# EIB_96Ch_YO.net
KiCad netlist of a schematic drawn in EAGLE
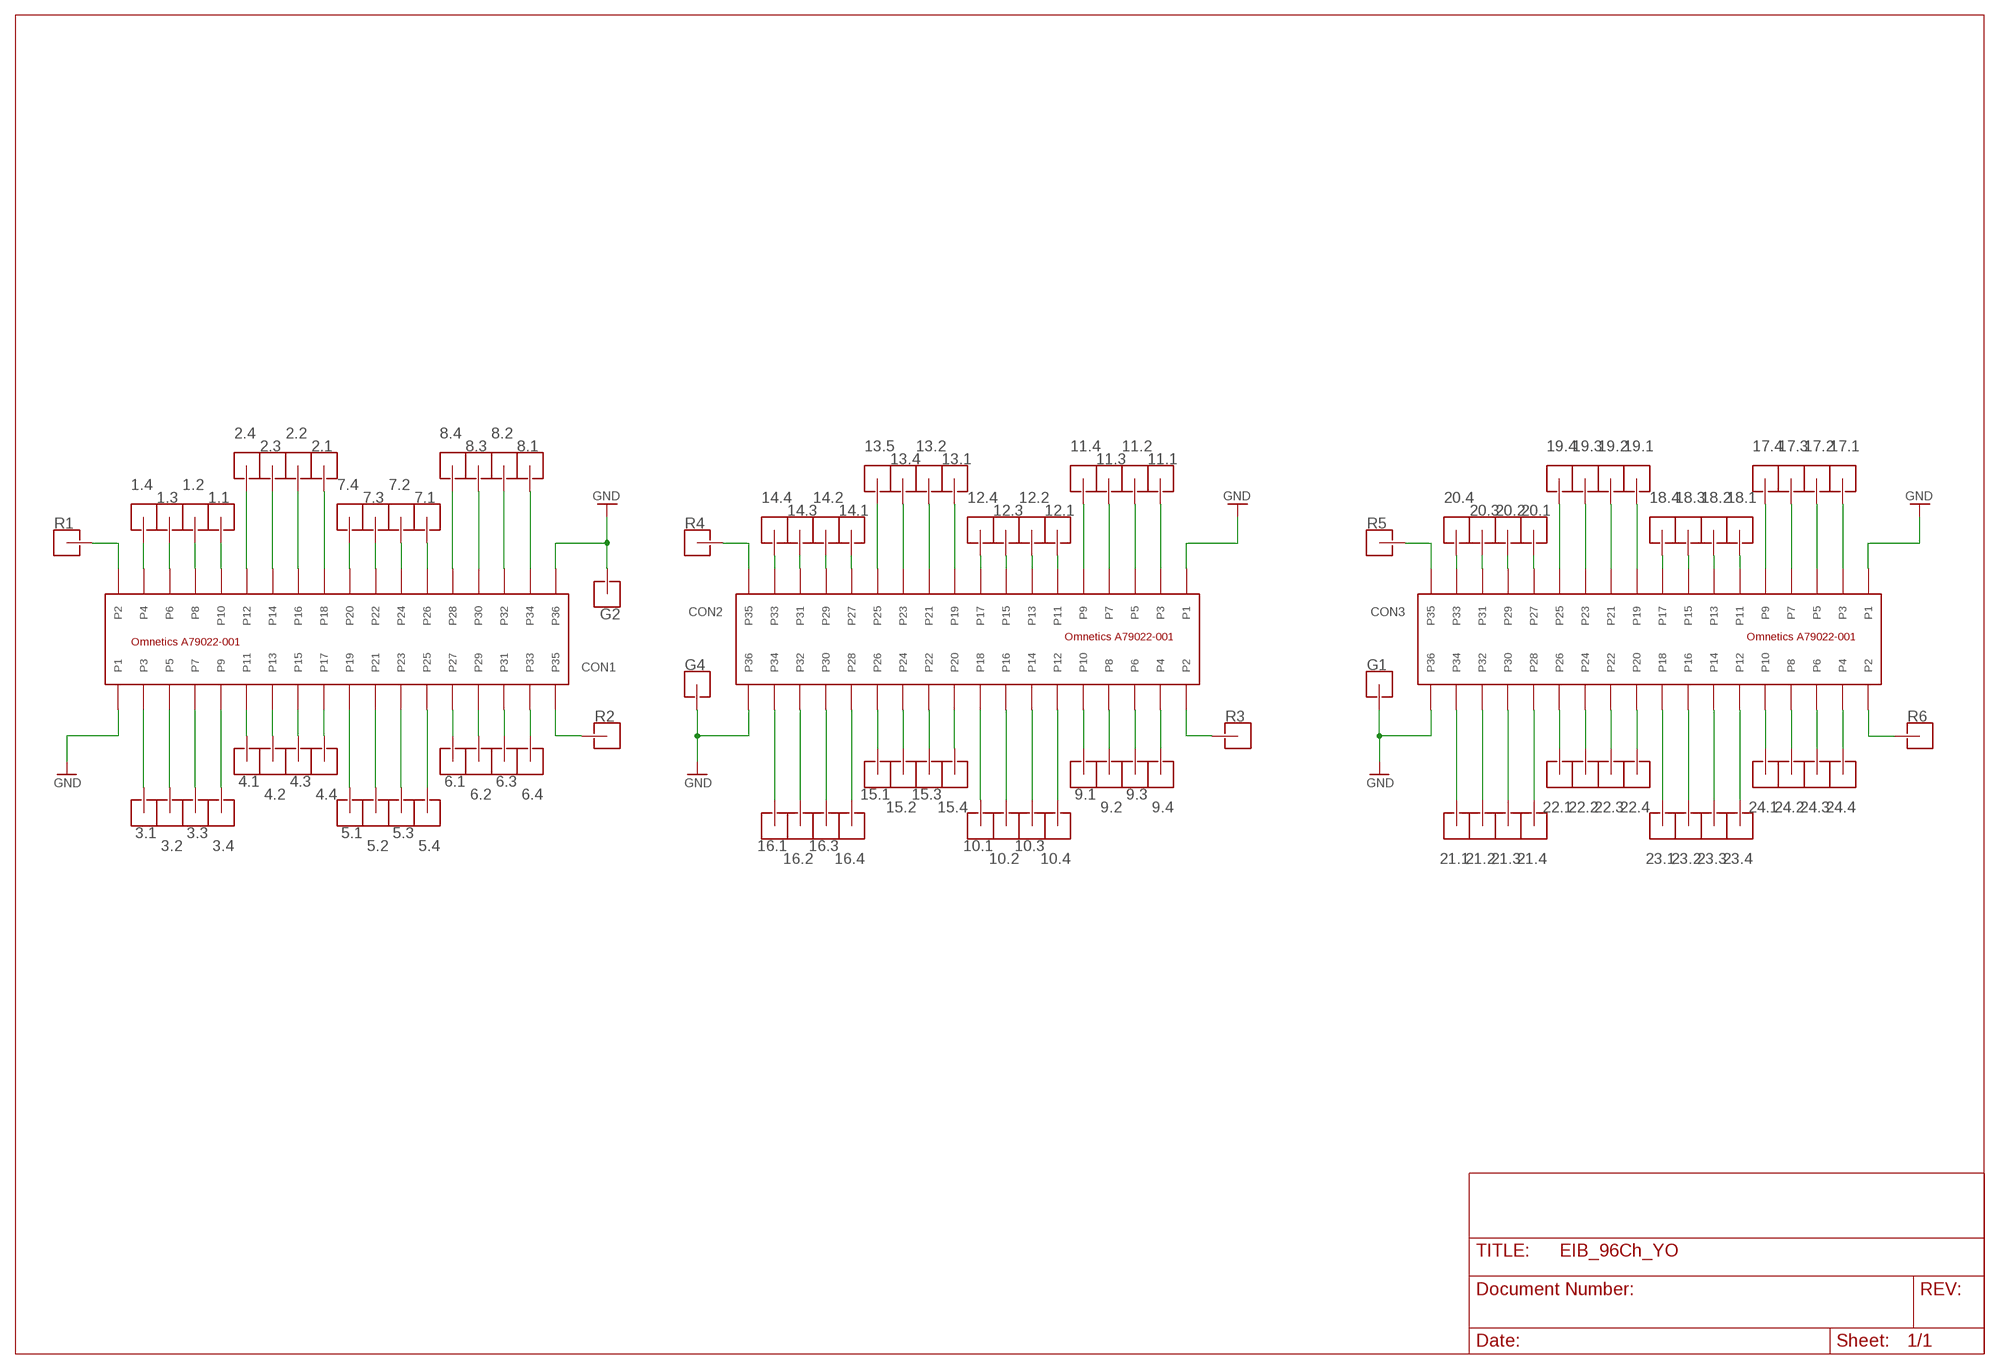
[diagram p0: schematic, sheet 1]

(export (version "E")
  (design (tool "Eeschema 10.0.6"))
  (components
    (comp (ref "1.1")
      (value "HOLE_L_G_PIN_V5")
      (footprint "eagle-import:LARGE_GOLD_PIN_V5")
      (libsource (lib "eagle-import") (part "HOLE_L_G_PIN_V5"))
    )
    (comp (ref "1.2")
      (value "HOLE_L_G_PIN_V5")
      (footprint "eagle-import:LARGE_GOLD_PIN_V5")
      (libsource (lib "eagle-import") (part "HOLE_L_G_PIN_V5"))
    )
    (comp (ref "1.3")
      (value "HOLE_L_G_PIN_V5")
      (footprint "eagle-import:LARGE_GOLD_PIN_V5")
      (libsource (lib "eagle-import") (part "HOLE_L_G_PIN_V5"))
    )
    (comp (ref "1.4")
      (value "HOLE_L_G_PIN_V5")
      (footprint "eagle-import:LARGE_GOLD_PIN_V5")
      (libsource (lib "eagle-import") (part "HOLE_L_G_PIN_V5"))
    )
    (comp (ref "2.1")
      (value "HOLE_L_G_PIN_V5")
      (footprint "eagle-import:LARGE_GOLD_PIN_V5")
      (libsource (lib "eagle-import") (part "HOLE_L_G_PIN_V5"))
    )
    (comp (ref "2.2")
      (value "HOLE_L_G_PIN_V5")
      (footprint "eagle-import:LARGE_GOLD_PIN_V5")
      (libsource (lib "eagle-import") (part "HOLE_L_G_PIN_V5"))
    )
    (comp (ref "2.3")
      (value "HOLE_L_G_PIN_V5")
      (footprint "eagle-import:LARGE_GOLD_PIN_V5")
      (libsource (lib "eagle-import") (part "HOLE_L_G_PIN_V5"))
    )
    (comp (ref "2.4")
      (value "HOLE_L_G_PIN_V5")
      (footprint "eagle-import:LARGE_GOLD_PIN_V5")
      (libsource (lib "eagle-import") (part "HOLE_L_G_PIN_V5"))
    )
    (comp (ref "3.1")
      (value "HOLE_L_G_PIN_V5")
      (footprint "eagle-import:LARGE_GOLD_PIN_V5")
      (libsource (lib "eagle-import") (part "HOLE_L_G_PIN_V5"))
    )
    (comp (ref "3.2")
      (value "HOLE_L_G_PIN_V5")
      (footprint "eagle-import:LARGE_GOLD_PIN_V5")
      (libsource (lib "eagle-import") (part "HOLE_L_G_PIN_V5"))
    )
    (comp (ref "3.3")
      (value "HOLE_L_G_PIN_V5")
      (footprint "eagle-import:LARGE_GOLD_PIN_V5")
      (libsource (lib "eagle-import") (part "HOLE_L_G_PIN_V5"))
    )
    (comp (ref "3.4")
      (value "HOLE_L_G_PIN_V5")
      (footprint "eagle-import:LARGE_GOLD_PIN_V5")
      (libsource (lib "eagle-import") (part "HOLE_L_G_PIN_V5"))
    )
    (comp (ref "4.1")
      (value "HOLE_L_G_PIN_V5")
      (footprint "eagle-import:LARGE_GOLD_PIN_V5")
      (libsource (lib "eagle-import") (part "HOLE_L_G_PIN_V5"))
    )
    (comp (ref "4.2")
      (value "HOLE_L_G_PIN_V5")
      (footprint "eagle-import:LARGE_GOLD_PIN_V5")
      (libsource (lib "eagle-import") (part "HOLE_L_G_PIN_V5"))
    )
    (comp (ref "4.3")
      (value "HOLE_L_G_PIN_V5")
      (footprint "eagle-import:LARGE_GOLD_PIN_V5")
      (libsource (lib "eagle-import") (part "HOLE_L_G_PIN_V5"))
    )
    (comp (ref "4.4")
      (value "HOLE_L_G_PIN_V5")
      (footprint "eagle-import:LARGE_GOLD_PIN_V5")
      (libsource (lib "eagle-import") (part "HOLE_L_G_PIN_V5"))
    )
    (comp (ref "5.1")
      (value "HOLE_L_G_PIN_V5")
      (footprint "eagle-import:LARGE_GOLD_PIN_V5")
      (libsource (lib "eagle-import") (part "HOLE_L_G_PIN_V5"))
    )
    (comp (ref "5.2")
      (value "HOLE_L_G_PIN_V5")
      (footprint "eagle-import:LARGE_GOLD_PIN_V5")
      (libsource (lib "eagle-import") (part "HOLE_L_G_PIN_V5"))
    )
    (comp (ref "5.3")
      (value "HOLE_L_G_PIN_V5")
      (footprint "eagle-import:LARGE_GOLD_PIN_V5")
      (libsource (lib "eagle-import") (part "HOLE_L_G_PIN_V5"))
    )
    (comp (ref "5.4")
      (value "HOLE_L_G_PIN_V5")
      (footprint "eagle-import:LARGE_GOLD_PIN_V5")
      (libsource (lib "eagle-import") (part "HOLE_L_G_PIN_V5"))
    )
    (comp (ref "6.1")
      (value "HOLE_L_G_PIN_V5")
      (footprint "eagle-import:LARGE_GOLD_PIN_V5")
      (libsource (lib "eagle-import") (part "HOLE_L_G_PIN_V5"))
    )
    (comp (ref "6.2")
      (value "HOLE_L_G_PIN_V5")
      (footprint "eagle-import:LARGE_GOLD_PIN_V5")
      (libsource (lib "eagle-import") (part "HOLE_L_G_PIN_V5"))
    )
    (comp (ref "6.3")
      (value "HOLE_L_G_PIN_V5")
      (footprint "eagle-import:LARGE_GOLD_PIN_V5")
      (libsource (lib "eagle-import") (part "HOLE_L_G_PIN_V5"))
    )
    (comp (ref "6.4")
      (value "HOLE_L_G_PIN_V5")
      (footprint "eagle-import:LARGE_GOLD_PIN_V5")
      (libsource (lib "eagle-import") (part "HOLE_L_G_PIN_V5"))
    )
    (comp (ref "7.1")
      (value "HOLE_L_G_PIN_V5")
      (footprint "eagle-import:LARGE_GOLD_PIN_V5")
      (libsource (lib "eagle-import") (part "HOLE_L_G_PIN_V5"))
    )
    (comp (ref "7.2")
      (value "HOLE_L_G_PIN_V5")
      (footprint "eagle-import:LARGE_GOLD_PIN_V5")
      (libsource (lib "eagle-import") (part "HOLE_L_G_PIN_V5"))
    )
    (comp (ref "7.3")
      (value "HOLE_L_G_PIN_V5")
      (footprint "eagle-import:LARGE_GOLD_PIN_V5")
      (libsource (lib "eagle-import") (part "HOLE_L_G_PIN_V5"))
    )
    (comp (ref "7.4")
      (value "HOLE_L_G_PIN_V5")
      (footprint "eagle-import:LARGE_GOLD_PIN_V5")
      (libsource (lib "eagle-import") (part "HOLE_L_G_PIN_V5"))
    )
    (comp (ref "8.1")
      (value "HOLE_L_G_PIN_V5")
      (footprint "eagle-import:LARGE_GOLD_PIN_V5")
      (libsource (lib "eagle-import") (part "HOLE_L_G_PIN_V5"))
    )
    (comp (ref "8.2")
      (value "HOLE_L_G_PIN_V5")
      (footprint "eagle-import:LARGE_GOLD_PIN_V5")
      (libsource (lib "eagle-import") (part "HOLE_L_G_PIN_V5"))
    )
    (comp (ref "8.3")
      (value "HOLE_L_G_PIN_V5")
      (footprint "eagle-import:LARGE_GOLD_PIN_V5")
      (libsource (lib "eagle-import") (part "HOLE_L_G_PIN_V5"))
    )
    (comp (ref "8.4")
      (value "HOLE_L_G_PIN_V5")
      (footprint "eagle-import:LARGE_GOLD_PIN_V5")
      (libsource (lib "eagle-import") (part "HOLE_L_G_PIN_V5"))
    )
    (comp (ref "9.1")
      (value "HOLE_L_G_PIN_V5")
      (footprint "eagle-import:LARGE_GOLD_PIN_V5")
      (libsource (lib "eagle-import") (part "HOLE_L_G_PIN_V5"))
    )
    (comp (ref "9.2")
      (value "HOLE_L_G_PIN_V5")
      (footprint "eagle-import:LARGE_GOLD_PIN_V5")
      (libsource (lib "eagle-import") (part "HOLE_L_G_PIN_V5"))
    )
    (comp (ref "9.3")
      (value "HOLE_L_G_PIN_V5")
      (footprint "eagle-import:LARGE_GOLD_PIN_V5")
      (libsource (lib "eagle-import") (part "HOLE_L_G_PIN_V5"))
    )
    (comp (ref "9.4")
      (value "HOLE_L_G_PIN_V5")
      (footprint "eagle-import:LARGE_GOLD_PIN_V5")
      (libsource (lib "eagle-import") (part "HOLE_L_G_PIN_V5"))
    )
    (comp (ref "10.1")
      (value "HOLE_L_G_PIN_V5")
      (footprint "eagle-import:LARGE_GOLD_PIN_V5")
      (libsource (lib "eagle-import") (part "HOLE_L_G_PIN_V5"))
    )
    (comp (ref "10.2")
      (value "HOLE_L_G_PIN_V5")
      (footprint "eagle-import:LARGE_GOLD_PIN_V5")
      (libsource (lib "eagle-import") (part "HOLE_L_G_PIN_V5"))
    )
    (comp (ref "10.3")
      (value "HOLE_L_G_PIN_V5")
      (footprint "eagle-import:LARGE_GOLD_PIN_V5")
      (libsource (lib "eagle-import") (part "HOLE_L_G_PIN_V5"))
    )
    (comp (ref "10.4")
      (value "HOLE_L_G_PIN_V5")
      (footprint "eagle-import:LARGE_GOLD_PIN_V5")
      (libsource (lib "eagle-import") (part "HOLE_L_G_PIN_V5"))
    )
    (comp (ref "11.1")
      (value "HOLE_L_G_PIN_V5")
      (footprint "eagle-import:LARGE_GOLD_PIN_V5")
      (libsource (lib "eagle-import") (part "HOLE_L_G_PIN_V5"))
    )
    (comp (ref "11.2")
      (value "HOLE_L_G_PIN_V5")
      (footprint "eagle-import:LARGE_GOLD_PIN_V5")
      (libsource (lib "eagle-import") (part "HOLE_L_G_PIN_V5"))
    )
    (comp (ref "11.3")
      (value "HOLE_L_G_PIN_V5")
      (footprint "eagle-import:LARGE_GOLD_PIN_V5")
      (libsource (lib "eagle-import") (part "HOLE_L_G_PIN_V5"))
    )
    (comp (ref "11.4")
      (value "HOLE_L_G_PIN_V5")
      (footprint "eagle-import:LARGE_GOLD_PIN_V5")
      (libsource (lib "eagle-import") (part "HOLE_L_G_PIN_V5"))
    )
    (comp (ref "12.1")
      (value "HOLE_L_G_PIN_V5")
      (footprint "eagle-import:LARGE_GOLD_PIN_V5")
      (libsource (lib "eagle-import") (part "HOLE_L_G_PIN_V5"))
    )
    (comp (ref "12.2")
      (value "HOLE_L_G_PIN_V5")
      (footprint "eagle-import:LARGE_GOLD_PIN_V5")
      (libsource (lib "eagle-import") (part "HOLE_L_G_PIN_V5"))
    )
    (comp (ref "12.3")
      (value "HOLE_L_G_PIN_V5")
      (footprint "eagle-import:LARGE_GOLD_PIN_V5")
      (libsource (lib "eagle-import") (part "HOLE_L_G_PIN_V5"))
    )
    (comp (ref "12.4")
      (value "HOLE_L_G_PIN_V5")
      (footprint "eagle-import:LARGE_GOLD_PIN_V5")
      (libsource (lib "eagle-import") (part "HOLE_L_G_PIN_V5"))
    )
    (comp (ref "13.1")
      (value "HOLE_L_G_PIN_V5")
      (footprint "eagle-import:LARGE_GOLD_PIN_V5")
      (libsource (lib "eagle-import") (part "HOLE_L_G_PIN_V5"))
    )
    (comp (ref "13.2")
      (value "HOLE_L_G_PIN_V5")
      (footprint "eagle-import:LARGE_GOLD_PIN_V5")
      (libsource (lib "eagle-import") (part "HOLE_L_G_PIN_V5"))
    )
    (comp (ref "13.4")
      (value "HOLE_L_G_PIN_V5")
      (footprint "eagle-import:LARGE_GOLD_PIN_V5")
      (libsource (lib "eagle-import") (part "HOLE_L_G_PIN_V5"))
    )
    (comp (ref "13.5")
      (value "HOLE_L_G_PIN_V5")
      (footprint "eagle-import:LARGE_GOLD_PIN_V5")
      (libsource (lib "eagle-import") (part "HOLE_L_G_PIN_V5"))
    )
    (comp (ref "14.1")
      (value "HOLE_L_G_PIN_V5")
      (footprint "eagle-import:LARGE_GOLD_PIN_V5")
      (libsource (lib "eagle-import") (part "HOLE_L_G_PIN_V5"))
    )
    (comp (ref "14.2")
      (value "HOLE_L_G_PIN_V5")
      (footprint "eagle-import:LARGE_GOLD_PIN_V5")
      (libsource (lib "eagle-import") (part "HOLE_L_G_PIN_V5"))
    )
    (comp (ref "14.3")
      (value "HOLE_L_G_PIN_V5")
      (footprint "eagle-import:LARGE_GOLD_PIN_V5")
      (libsource (lib "eagle-import") (part "HOLE_L_G_PIN_V5"))
    )
    (comp (ref "14.4")
      (value "HOLE_L_G_PIN_V5")
      (footprint "eagle-import:LARGE_GOLD_PIN_V5")
      (libsource (lib "eagle-import") (part "HOLE_L_G_PIN_V5"))
    )
    (comp (ref "15.1")
      (value "HOLE_L_G_PIN_V5")
      (footprint "eagle-import:LARGE_GOLD_PIN_V5")
      (libsource (lib "eagle-import") (part "HOLE_L_G_PIN_V5"))
    )
    (comp (ref "15.2")
      (value "HOLE_L_G_PIN_V5")
      (footprint "eagle-import:LARGE_GOLD_PIN_V5")
      (libsource (lib "eagle-import") (part "HOLE_L_G_PIN_V5"))
    )
    (comp (ref "15.3")
      (value "HOLE_L_G_PIN_V5")
      (footprint "eagle-import:LARGE_GOLD_PIN_V5")
      (libsource (lib "eagle-import") (part "HOLE_L_G_PIN_V5"))
    )
    (comp (ref "15.4")
      (value "HOLE_L_G_PIN_V5")
      (footprint "eagle-import:LARGE_GOLD_PIN_V5")
      (libsource (lib "eagle-import") (part "HOLE_L_G_PIN_V5"))
    )
    (comp (ref "16.1")
      (value "HOLE_L_G_PIN_V5")
      (footprint "eagle-import:LARGE_GOLD_PIN_V5")
      (libsource (lib "eagle-import") (part "HOLE_L_G_PIN_V5"))
    )
    (comp (ref "16.2")
      (value "HOLE_L_G_PIN_V5")
      (footprint "eagle-import:LARGE_GOLD_PIN_V5")
      (libsource (lib "eagle-import") (part "HOLE_L_G_PIN_V5"))
    )
    (comp (ref "16.3")
      (value "HOLE_L_G_PIN_V5")
      (footprint "eagle-import:LARGE_GOLD_PIN_V5")
      (libsource (lib "eagle-import") (part "HOLE_L_G_PIN_V5"))
    )
    (comp (ref "16.4")
      (value "HOLE_L_G_PIN_V5")
      (footprint "eagle-import:LARGE_GOLD_PIN_V5")
      (libsource (lib "eagle-import") (part "HOLE_L_G_PIN_V5"))
    )
    (comp (ref "17.1")
      (value "HOLE_L_G_PIN_V5")
      (footprint "eagle-import:LARGE_GOLD_PIN_V5")
      (libsource (lib "eagle-import") (part "HOLE_L_G_PIN_V5"))
    )
    (comp (ref "17.2")
      (value "HOLE_L_G_PIN_V5")
      (footprint "eagle-import:LARGE_GOLD_PIN_V5")
      (libsource (lib "eagle-import") (part "HOLE_L_G_PIN_V5"))
    )
    (comp (ref "17.3")
      (value "HOLE_L_G_PIN_V5")
      (footprint "eagle-import:LARGE_GOLD_PIN_V5")
      (libsource (lib "eagle-import") (part "HOLE_L_G_PIN_V5"))
    )
    (comp (ref "17.4")
      (value "HOLE_L_G_PIN_V5")
      (footprint "eagle-import:LARGE_GOLD_PIN_V5")
      (libsource (lib "eagle-import") (part "HOLE_L_G_PIN_V5"))
    )
    (comp (ref "18.1")
      (value "HOLE_L_G_PIN_V5")
      (footprint "eagle-import:LARGE_GOLD_PIN_V5")
      (libsource (lib "eagle-import") (part "HOLE_L_G_PIN_V5"))
    )
    (comp (ref "18.2")
      (value "HOLE_L_G_PIN_V5")
      (footprint "eagle-import:LARGE_GOLD_PIN_V5")
      (libsource (lib "eagle-import") (part "HOLE_L_G_PIN_V5"))
    )
    (comp (ref "18.3")
      (value "HOLE_L_G_PIN_V5")
      (footprint "eagle-import:LARGE_GOLD_PIN_V5")
      (libsource (lib "eagle-import") (part "HOLE_L_G_PIN_V5"))
    )
    (comp (ref "18.4")
      (value "HOLE_L_G_PIN_V5")
      (footprint "eagle-import:LARGE_GOLD_PIN_V5")
      (libsource (lib "eagle-import") (part "HOLE_L_G_PIN_V5"))
    )
    (comp (ref "19.1")
      (value "HOLE_L_G_PIN_V5")
      (footprint "eagle-import:LARGE_GOLD_PIN_V5")
      (libsource (lib "eagle-import") (part "HOLE_L_G_PIN_V5"))
    )
    (comp (ref "19.2")
      (value "HOLE_L_G_PIN_V5")
      (footprint "eagle-import:LARGE_GOLD_PIN_V5")
      (libsource (lib "eagle-import") (part "HOLE_L_G_PIN_V5"))
    )
    (comp (ref "19.3")
      (value "HOLE_L_G_PIN_V5")
      (footprint "eagle-import:LARGE_GOLD_PIN_V5")
      (libsource (lib "eagle-import") (part "HOLE_L_G_PIN_V5"))
    )
    (comp (ref "19.4")
      (value "HOLE_L_G_PIN_V5")
      (footprint "eagle-import:LARGE_GOLD_PIN_V5")
      (libsource (lib "eagle-import") (part "HOLE_L_G_PIN_V5"))
    )
    (comp (ref "20.1")
      (value "HOLE_L_G_PIN_V5")
      (footprint "eagle-import:LARGE_GOLD_PIN_V5")
      (libsource (lib "eagle-import") (part "HOLE_L_G_PIN_V5"))
    )
    (comp (ref "20.2")
      (value "HOLE_L_G_PIN_V5")
      (footprint "eagle-import:LARGE_GOLD_PIN_V5")
      (libsource (lib "eagle-import") (part "HOLE_L_G_PIN_V5"))
    )
    (comp (ref "20.3")
      (value "HOLE_L_G_PIN_V5")
      (footprint "eagle-import:LARGE_GOLD_PIN_V5")
      (libsource (lib "eagle-import") (part "HOLE_L_G_PIN_V5"))
    )
    (comp (ref "20.4")
      (value "HOLE_L_G_PIN_V5")
      (footprint "eagle-import:LARGE_GOLD_PIN_V5")
      (libsource (lib "eagle-import") (part "HOLE_L_G_PIN_V5"))
    )
    (comp (ref "21.1")
      (value "HOLE_L_G_PIN_V5")
      (footprint "eagle-import:LARGE_GOLD_PIN_V5")
      (libsource (lib "eagle-import") (part "HOLE_L_G_PIN_V5"))
    )
    (comp (ref "21.2")
      (value "HOLE_L_G_PIN_V5")
      (footprint "eagle-import:LARGE_GOLD_PIN_V5")
      (libsource (lib "eagle-import") (part "HOLE_L_G_PIN_V5"))
    )
    (comp (ref "21.3")
      (value "HOLE_L_G_PIN_V5")
      (footprint "eagle-import:LARGE_GOLD_PIN_V5")
      (libsource (lib "eagle-import") (part "HOLE_L_G_PIN_V5"))
    )
    (comp (ref "21.4")
      (value "HOLE_L_G_PIN_V5")
      (footprint "eagle-import:LARGE_GOLD_PIN_V5")
      (libsource (lib "eagle-import") (part "HOLE_L_G_PIN_V5"))
    )
    (comp (ref "22.1")
      (value "HOLE_L_G_PIN_V5")
      (footprint "eagle-import:LARGE_GOLD_PIN_V5")
      (libsource (lib "eagle-import") (part "HOLE_L_G_PIN_V5"))
    )
    (comp (ref "22.2")
      (value "HOLE_L_G_PIN_V5")
      (footprint "eagle-import:LARGE_GOLD_PIN_V5")
      (libsource (lib "eagle-import") (part "HOLE_L_G_PIN_V5"))
    )
    (comp (ref "22.3")
      (value "HOLE_L_G_PIN_V5")
      (footprint "eagle-import:LARGE_GOLD_PIN_V5")
      (libsource (lib "eagle-import") (part "HOLE_L_G_PIN_V5"))
    )
    (comp (ref "22.4")
      (value "HOLE_L_G_PIN_V5")
      (footprint "eagle-import:LARGE_GOLD_PIN_V5")
      (libsource (lib "eagle-import") (part "HOLE_L_G_PIN_V5"))
    )
    (comp (ref "23.1")
      (value "HOLE_L_G_PIN_V5")
      (footprint "eagle-import:LARGE_GOLD_PIN_V5")
      (libsource (lib "eagle-import") (part "HOLE_L_G_PIN_V5"))
    )
    (comp (ref "23.2")
      (value "HOLE_L_G_PIN_V5")
      (footprint "eagle-import:LARGE_GOLD_PIN_V5")
      (libsource (lib "eagle-import") (part "HOLE_L_G_PIN_V5"))
    )
    (comp (ref "23.3")
      (value "HOLE_L_G_PIN_V5")
      (footprint "eagle-import:LARGE_GOLD_PIN_V5")
      (libsource (lib "eagle-import") (part "HOLE_L_G_PIN_V5"))
    )
    (comp (ref "23.4")
      (value "HOLE_L_G_PIN_V5")
      (footprint "eagle-import:LARGE_GOLD_PIN_V5")
      (libsource (lib "eagle-import") (part "HOLE_L_G_PIN_V5"))
    )
    (comp (ref "24.1")
      (value "HOLE_L_G_PIN_V5")
      (footprint "eagle-import:LARGE_GOLD_PIN_V5")
      (libsource (lib "eagle-import") (part "HOLE_L_G_PIN_V5"))
    )
    (comp (ref "24.2")
      (value "HOLE_L_G_PIN_V5")
      (footprint "eagle-import:LARGE_GOLD_PIN_V5")
      (libsource (lib "eagle-import") (part "HOLE_L_G_PIN_V5"))
    )
    (comp (ref "24.3")
      (value "HOLE_L_G_PIN_V5")
      (footprint "eagle-import:LARGE_GOLD_PIN_V5")
      (libsource (lib "eagle-import") (part "HOLE_L_G_PIN_V5"))
    )
    (comp (ref "24.4")
      (value "HOLE_L_G_PIN_V5")
      (footprint "eagle-import:LARGE_GOLD_PIN_V5")
      (libsource (lib "eagle-import") (part "HOLE_L_G_PIN_V5"))
    )
    (comp (ref "CON1")
      (value "A79022-001_MALESMD")
      (footprint "eagle-import:A79026-001_MALE")
      (libsource (lib "eagle-import") (part "A79022-001_MALESMD"))
    )
    (comp (ref "CON2")
      (value "A79022-001_MALESMD")
      (footprint "eagle-import:A79026-001_MALE")
      (libsource (lib "eagle-import") (part "A79022-001_MALESMD"))
    )
    (comp (ref "CON3")
      (value "A79022-001_MALESMD")
      (footprint "eagle-import:A79026-001_MALE")
      (libsource (lib "eagle-import") (part "A79022-001_MALESMD"))
    )
    (comp (ref "G1")
      (value "HOLE_L_G_PIN_V5")
      (footprint "eagle-import:LARGE_GOLD_PIN_V5")
      (libsource (lib "eagle-import") (part "HOLE_L_G_PIN_V5"))
    )
    (comp (ref "G2")
      (value "HOLE_L_G_PIN_V5")
      (footprint "eagle-import:LARGE_GOLD_PIN_V5")
      (libsource (lib "eagle-import") (part "HOLE_L_G_PIN_V5"))
    )
    (comp (ref "G4")
      (value "HOLE_L_G_PIN_V5")
      (footprint "eagle-import:LARGE_GOLD_PIN_V5")
      (libsource (lib "eagle-import") (part "HOLE_L_G_PIN_V5"))
    )
    (comp (ref "R1")
      (value "HOLE_L_G_PIN_V5")
      (footprint "eagle-import:LARGE_GOLD_PIN_V5")
      (libsource (lib "eagle-import") (part "HOLE_L_G_PIN_V5"))
    )
    (comp (ref "R2")
      (value "HOLE_L_G_PIN_V5")
      (footprint "eagle-import:LARGE_GOLD_PIN_V5")
      (libsource (lib "eagle-import") (part "HOLE_L_G_PIN_V5"))
    )
    (comp (ref "R3")
      (value "HOLE_L_G_PIN_V5")
      (footprint "eagle-import:LARGE_GOLD_PIN_V5")
      (libsource (lib "eagle-import") (part "HOLE_L_G_PIN_V5"))
    )
    (comp (ref "R4")
      (value "HOLE_L_G_PIN_V5")
      (footprint "eagle-import:LARGE_GOLD_PIN_V5")
      (libsource (lib "eagle-import") (part "HOLE_L_G_PIN_V5"))
    )
    (comp (ref "R5")
      (value "HOLE_L_G_PIN_V5")
      (footprint "eagle-import:LARGE_GOLD_PIN_V5")
      (libsource (lib "eagle-import") (part "HOLE_L_G_PIN_V5"))
    )
    (comp (ref "R6")
      (value "HOLE_L_G_PIN_V5")
      (footprint "eagle-import:LARGE_GOLD_PIN_V5")
      (libsource (lib "eagle-import") (part "HOLE_L_G_PIN_V5"))
    )
  )
  (nets
    (net (code "1") (name "GND") (class "Default")
      (node (ref "CON1") (pin "P1") (pinfunction "P1_P1") (pintype "bidirectional"))
      (node (ref "CON1") (pin "P36") (pinfunction "P36_P36") (pintype "bidirectional"))
      (node (ref "CON2") (pin "P1") (pinfunction "P1_P1") (pintype "bidirectional"))
      (node (ref "CON2") (pin "P36") (pinfunction "P36_P36") (pintype "bidirectional"))
      (node (ref "CON3") (pin "P1") (pinfunction "P1_P1") (pintype "bidirectional"))
      (node (ref "CON3") (pin "P36") (pinfunction "P36_P36") (pintype "bidirectional"))
      (node (ref "G1") (pin "P$1") (pinfunction "P$1_P$1") (pintype "bidirectional"))
      (node (ref "G2") (pin "P$1") (pinfunction "P$1_P$1") (pintype "bidirectional"))
      (node (ref "G4") (pin "P$1") (pinfunction "P$1_P$1") (pintype "bidirectional"))
    )
    (net (code "2") (name "Net-(1.1-PadP$1)") (class "Default")
      (node (ref "1.1") (pin "P$1") (pinfunction "P$1_P$1") (pintype "bidirectional"))
      (node (ref "CON1") (pin "P10") (pinfunction "P10_P10") (pintype "bidirectional"))
    )
    (net (code "3") (name "Net-(1.2-PadP$1)") (class "Default")
      (node (ref "1.2") (pin "P$1") (pinfunction "P$1_P$1") (pintype "bidirectional"))
      (node (ref "CON1") (pin "P8") (pinfunction "P8_P8") (pintype "bidirectional"))
    )
    (net (code "4") (name "Net-(1.3-PadP$1)") (class "Default")
      (node (ref "1.3") (pin "P$1") (pinfunction "P$1_P$1") (pintype "bidirectional"))
      (node (ref "CON1") (pin "P6") (pinfunction "P6_P6") (pintype "bidirectional"))
    )
    (net (code "5") (name "Net-(1.4-PadP$1)") (class "Default")
      (node (ref "1.4") (pin "P$1") (pinfunction "P$1_P$1") (pintype "bidirectional"))
      (node (ref "CON1") (pin "P4") (pinfunction "P4_P4") (pintype "bidirectional"))
    )
    (net (code "6") (name "Net-(2.1-PadP$1)") (class "Default")
      (node (ref "2.1") (pin "P$1") (pinfunction "P$1_P$1") (pintype "bidirectional"))
      (node (ref "CON1") (pin "P18") (pinfunction "P18_P18") (pintype "bidirectional"))
    )
    (net (code "7") (name "Net-(2.2-PadP$1)") (class "Default")
      (node (ref "2.2") (pin "P$1") (pinfunction "P$1_P$1") (pintype "bidirectional"))
      (node (ref "CON1") (pin "P16") (pinfunction "P16_P16") (pintype "bidirectional"))
    )
    (net (code "8") (name "Net-(2.3-PadP$1)") (class "Default")
      (node (ref "2.3") (pin "P$1") (pinfunction "P$1_P$1") (pintype "bidirectional"))
      (node (ref "CON1") (pin "P14") (pinfunction "P14_P14") (pintype "bidirectional"))
    )
    (net (code "9") (name "Net-(2.4-PadP$1)") (class "Default")
      (node (ref "2.4") (pin "P$1") (pinfunction "P$1_P$1") (pintype "bidirectional"))
      (node (ref "CON1") (pin "P12") (pinfunction "P12_P12") (pintype "bidirectional"))
    )
    (net (code "10") (name "Net-(3.1-PadP$1)") (class "Default")
      (node (ref "3.1") (pin "P$1") (pinfunction "P$1_P$1") (pintype "bidirectional"))
      (node (ref "CON1") (pin "P3") (pinfunction "P3_P3") (pintype "bidirectional"))
    )
    (net (code "11") (name "Net-(3.2-PadP$1)") (class "Default")
      (node (ref "3.2") (pin "P$1") (pinfunction "P$1_P$1") (pintype "bidirectional"))
      (node (ref "CON1") (pin "P5") (pinfunction "P5_P5") (pintype "bidirectional"))
    )
    (net (code "12") (name "Net-(3.3-PadP$1)") (class "Default")
      (node (ref "3.3") (pin "P$1") (pinfunction "P$1_P$1") (pintype "bidirectional"))
      (node (ref "CON1") (pin "P7") (pinfunction "P7_P7") (pintype "bidirectional"))
    )
    (net (code "13") (name "Net-(3.4-PadP$1)") (class "Default")
      (node (ref "3.4") (pin "P$1") (pinfunction "P$1_P$1") (pintype "bidirectional"))
      (node (ref "CON1") (pin "P9") (pinfunction "P9_P9") (pintype "bidirectional"))
    )
    (net (code "14") (name "Net-(4.1-PadP$1)") (class "Default")
      (node (ref "4.1") (pin "P$1") (pinfunction "P$1_P$1") (pintype "bidirectional"))
      (node (ref "CON1") (pin "P11") (pinfunction "P11_P11") (pintype "bidirectional"))
    )
    (net (code "15") (name "Net-(4.2-PadP$1)") (class "Default")
      (node (ref "4.2") (pin "P$1") (pinfunction "P$1_P$1") (pintype "bidirectional"))
      (node (ref "CON1") (pin "P13") (pinfunction "P13_P13") (pintype "bidirectional"))
    )
    (net (code "16") (name "Net-(4.3-PadP$1)") (class "Default")
      (node (ref "4.3") (pin "P$1") (pinfunction "P$1_P$1") (pintype "bidirectional"))
      (node (ref "CON1") (pin "P15") (pinfunction "P15_P15") (pintype "bidirectional"))
    )
    (net (code "17") (name "Net-(4.4-PadP$1)") (class "Default")
      (node (ref "4.4") (pin "P$1") (pinfunction "P$1_P$1") (pintype "bidirectional"))
      (node (ref "CON1") (pin "P17") (pinfunction "P17_P17") (pintype "bidirectional"))
    )
    (net (code "18") (name "Net-(5.1-PadP$1)") (class "Default")
      (node (ref "5.1") (pin "P$1") (pinfunction "P$1_P$1") (pintype "bidirectional"))
      (node (ref "CON1") (pin "P19") (pinfunction "P19_P19") (pintype "bidirectional"))
    )
    (net (code "19") (name "Net-(5.2-PadP$1)") (class "Default")
      (node (ref "5.2") (pin "P$1") (pinfunction "P$1_P$1") (pintype "bidirectional"))
      (node (ref "CON1") (pin "P21") (pinfunction "P21_P21") (pintype "bidirectional"))
    )
    (net (code "20") (name "Net-(5.3-PadP$1)") (class "Default")
      (node (ref "5.3") (pin "P$1") (pinfunction "P$1_P$1") (pintype "bidirectional"))
      (node (ref "CON1") (pin "P23") (pinfunction "P23_P23") (pintype "bidirectional"))
    )
    (net (code "21") (name "Net-(5.4-PadP$1)") (class "Default")
      (node (ref "5.4") (pin "P$1") (pinfunction "P$1_P$1") (pintype "bidirectional"))
      (node (ref "CON1") (pin "P25") (pinfunction "P25_P25") (pintype "bidirectional"))
    )
    (net (code "22") (name "Net-(6.1-PadP$1)") (class "Default")
      (node (ref "6.1") (pin "P$1") (pinfunction "P$1_P$1") (pintype "bidirectional"))
      (node (ref "CON1") (pin "P27") (pinfunction "P27_P27") (pintype "bidirectional"))
    )
    (net (code "23") (name "Net-(6.2-PadP$1)") (class "Default")
      (node (ref "6.2") (pin "P$1") (pinfunction "P$1_P$1") (pintype "bidirectional"))
      (node (ref "CON1") (pin "P29") (pinfunction "P29_P29") (pintype "bidirectional"))
    )
    (net (code "24") (name "Net-(6.3-PadP$1)") (class "Default")
      (node (ref "6.3") (pin "P$1") (pinfunction "P$1_P$1") (pintype "bidirectional"))
      (node (ref "CON1") (pin "P31") (pinfunction "P31_P31") (pintype "bidirectional"))
    )
    (net (code "25") (name "Net-(6.4-PadP$1)") (class "Default")
      (node (ref "6.4") (pin "P$1") (pinfunction "P$1_P$1") (pintype "bidirectional"))
      (node (ref "CON1") (pin "P33") (pinfunction "P33_P33") (pintype "bidirectional"))
    )
    (net (code "26") (name "Net-(7.1-PadP$1)") (class "Default")
      (node (ref "7.1") (pin "P$1") (pinfunction "P$1_P$1") (pintype "bidirectional"))
      (node (ref "CON1") (pin "P26") (pinfunction "P26_P26") (pintype "bidirectional"))
    )
    (net (code "27") (name "Net-(7.2-PadP$1)") (class "Default")
      (node (ref "7.2") (pin "P$1") (pinfunction "P$1_P$1") (pintype "bidirectional"))
      (node (ref "CON1") (pin "P24") (pinfunction "P24_P24") (pintype "bidirectional"))
    )
    (net (code "28") (name "Net-(7.3-PadP$1)") (class "Default")
      (node (ref "7.3") (pin "P$1") (pinfunction "P$1_P$1") (pintype "bidirectional"))
      (node (ref "CON1") (pin "P22") (pinfunction "P22_P22") (pintype "bidirectional"))
    )
    (net (code "29") (name "Net-(7.4-PadP$1)") (class "Default")
      (node (ref "7.4") (pin "P$1") (pinfunction "P$1_P$1") (pintype "bidirectional"))
      (node (ref "CON1") (pin "P20") (pinfunction "P20_P20") (pintype "bidirectional"))
    )
    (net (code "30") (name "Net-(8.1-PadP$1)") (class "Default")
      (node (ref "8.1") (pin "P$1") (pinfunction "P$1_P$1") (pintype "bidirectional"))
      (node (ref "CON1") (pin "P34") (pinfunction "P34_P34") (pintype "bidirectional"))
    )
    (net (code "31") (name "Net-(8.2-PadP$1)") (class "Default")
      (node (ref "8.2") (pin "P$1") (pinfunction "P$1_P$1") (pintype "bidirectional"))
      (node (ref "CON1") (pin "P32") (pinfunction "P32_P32") (pintype "bidirectional"))
    )
    (net (code "32") (name "Net-(8.3-PadP$1)") (class "Default")
      (node (ref "8.3") (pin "P$1") (pinfunction "P$1_P$1") (pintype "bidirectional"))
      (node (ref "CON1") (pin "P30") (pinfunction "P30_P30") (pintype "bidirectional"))
    )
    (net (code "33") (name "Net-(8.4-PadP$1)") (class "Default")
      (node (ref "8.4") (pin "P$1") (pinfunction "P$1_P$1") (pintype "bidirectional"))
      (node (ref "CON1") (pin "P28") (pinfunction "P28_P28") (pintype "bidirectional"))
    )
    (net (code "34") (name "Net-(9.1-PadP$1)") (class "Default")
      (node (ref "9.1") (pin "P$1") (pinfunction "P$1_P$1") (pintype "bidirectional"))
      (node (ref "CON2") (pin "P10") (pinfunction "P10_P10") (pintype "bidirectional"))
    )
    (net (code "35") (name "Net-(9.2-PadP$1)") (class "Default")
      (node (ref "9.2") (pin "P$1") (pinfunction "P$1_P$1") (pintype "bidirectional"))
      (node (ref "CON2") (pin "P8") (pinfunction "P8_P8") (pintype "bidirectional"))
    )
    (net (code "36") (name "Net-(9.3-PadP$1)") (class "Default")
      (node (ref "9.3") (pin "P$1") (pinfunction "P$1_P$1") (pintype "bidirectional"))
      (node (ref "CON2") (pin "P6") (pinfunction "P6_P6") (pintype "bidirectional"))
    )
    (net (code "37") (name "Net-(9.4-PadP$1)") (class "Default")
      (node (ref "9.4") (pin "P$1") (pinfunction "P$1_P$1") (pintype "bidirectional"))
      (node (ref "CON2") (pin "P4") (pinfunction "P4_P4") (pintype "bidirectional"))
    )
    (net (code "38") (name "Net-(10.1-PadP$1)") (class "Default")
      (node (ref "10.1") (pin "P$1") (pinfunction "P$1_P$1") (pintype "bidirectional"))
      (node (ref "CON2") (pin "P18") (pinfunction "P18_P18") (pintype "bidirectional"))
    )
    (net (code "39") (name "Net-(10.2-PadP$1)") (class "Default")
      (node (ref "10.2") (pin "P$1") (pinfunction "P$1_P$1") (pintype "bidirectional"))
      (node (ref "CON2") (pin "P16") (pinfunction "P16_P16") (pintype "bidirectional"))
    )
    (net (code "40") (name "Net-(10.3-PadP$1)") (class "Default")
      (node (ref "10.3") (pin "P$1") (pinfunction "P$1_P$1") (pintype "bidirectional"))
      (node (ref "CON2") (pin "P14") (pinfunction "P14_P14") (pintype "bidirectional"))
    )
    (net (code "41") (name "Net-(10.4-PadP$1)") (class "Default")
      (node (ref "10.4") (pin "P$1") (pinfunction "P$1_P$1") (pintype "bidirectional"))
      (node (ref "CON2") (pin "P12") (pinfunction "P12_P12") (pintype "bidirectional"))
    )
    (net (code "42") (name "Net-(11.1-PadP$1)") (class "Default")
      (node (ref "11.1") (pin "P$1") (pinfunction "P$1_P$1") (pintype "bidirectional"))
      (node (ref "CON2") (pin "P3") (pinfunction "P3_P3") (pintype "bidirectional"))
    )
    (net (code "43") (name "Net-(11.2-PadP$1)") (class "Default")
      (node (ref "11.2") (pin "P$1") (pinfunction "P$1_P$1") (pintype "bidirectional"))
      (node (ref "CON2") (pin "P5") (pinfunction "P5_P5") (pintype "bidirectional"))
    )
    (net (code "44") (name "Net-(11.3-PadP$1)") (class "Default")
      (node (ref "11.3") (pin "P$1") (pinfunction "P$1_P$1") (pintype "bidirectional"))
      (node (ref "CON2") (pin "P7") (pinfunction "P7_P7") (pintype "bidirectional"))
    )
    (net (code "45") (name "Net-(11.4-PadP$1)") (class "Default")
      (node (ref "11.4") (pin "P$1") (pinfunction "P$1_P$1") (pintype "bidirectional"))
      (node (ref "CON2") (pin "P9") (pinfunction "P9_P9") (pintype "bidirectional"))
    )
    (net (code "46") (name "Net-(12.1-PadP$1)") (class "Default")
      (node (ref "12.1") (pin "P$1") (pinfunction "P$1_P$1") (pintype "bidirectional"))
      (node (ref "CON2") (pin "P11") (pinfunction "P11_P11") (pintype "bidirectional"))
    )
    (net (code "47") (name "Net-(12.2-PadP$1)") (class "Default")
      (node (ref "12.2") (pin "P$1") (pinfunction "P$1_P$1") (pintype "bidirectional"))
      (node (ref "CON2") (pin "P13") (pinfunction "P13_P13") (pintype "bidirectional"))
    )
    (net (code "48") (name "Net-(12.3-PadP$1)") (class "Default")
      (node (ref "12.3") (pin "P$1") (pinfunction "P$1_P$1") (pintype "bidirectional"))
      (node (ref "CON2") (pin "P15") (pinfunction "P15_P15") (pintype "bidirectional"))
    )
    (net (code "49") (name "Net-(12.4-PadP$1)") (class "Default")
      (node (ref "12.4") (pin "P$1") (pinfunction "P$1_P$1") (pintype "bidirectional"))
      (node (ref "CON2") (pin "P17") (pinfunction "P17_P17") (pintype "bidirectional"))
    )
    (net (code "50") (name "Net-(13.1-PadP$1)") (class "Default")
      (node (ref "13.1") (pin "P$1") (pinfunction "P$1_P$1") (pintype "bidirectional"))
      (node (ref "CON2") (pin "P19") (pinfunction "P19_P19") (pintype "bidirectional"))
    )
    (net (code "51") (name "Net-(13.2-PadP$1)") (class "Default")
      (node (ref "13.2") (pin "P$1") (pinfunction "P$1_P$1") (pintype "bidirectional"))
      (node (ref "CON2") (pin "P21") (pinfunction "P21_P21") (pintype "bidirectional"))
    )
    (net (code "52") (name "Net-(13.4-PadP$1)") (class "Default")
      (node (ref "13.4") (pin "P$1") (pinfunction "P$1_P$1") (pintype "bidirectional"))
      (node (ref "CON2") (pin "P23") (pinfunction "P23_P23") (pintype "bidirectional"))
    )
    (net (code "53") (name "Net-(13.5-PadP$1)") (class "Default")
      (node (ref "13.5") (pin "P$1") (pinfunction "P$1_P$1") (pintype "bidirectional"))
      (node (ref "CON2") (pin "P25") (pinfunction "P25_P25") (pintype "bidirectional"))
    )
    (net (code "54") (name "Net-(14.1-PadP$1)") (class "Default")
      (node (ref "14.1") (pin "P$1") (pinfunction "P$1_P$1") (pintype "bidirectional"))
      (node (ref "CON2") (pin "P27") (pinfunction "P27_P27") (pintype "bidirectional"))
    )
    (net (code "55") (name "Net-(14.2-PadP$1)") (class "Default")
      (node (ref "14.2") (pin "P$1") (pinfunction "P$1_P$1") (pintype "bidirectional"))
      (node (ref "CON2") (pin "P29") (pinfunction "P29_P29") (pintype "bidirectional"))
    )
    (net (code "56") (name "Net-(14.3-PadP$1)") (class "Default")
      (node (ref "14.3") (pin "P$1") (pinfunction "P$1_P$1") (pintype "bidirectional"))
      (node (ref "CON2") (pin "P31") (pinfunction "P31_P31") (pintype "bidirectional"))
    )
    (net (code "57") (name "Net-(14.4-PadP$1)") (class "Default")
      (node (ref "14.4") (pin "P$1") (pinfunction "P$1_P$1") (pintype "bidirectional"))
      (node (ref "CON2") (pin "P33") (pinfunction "P33_P33") (pintype "bidirectional"))
    )
    (net (code "58") (name "Net-(15.1-PadP$1)") (class "Default")
      (node (ref "15.1") (pin "P$1") (pinfunction "P$1_P$1") (pintype "bidirectional"))
      (node (ref "CON2") (pin "P26") (pinfunction "P26_P26") (pintype "bidirectional"))
    )
    (net (code "59") (name "Net-(15.2-PadP$1)") (class "Default")
      (node (ref "15.2") (pin "P$1") (pinfunction "P$1_P$1") (pintype "bidirectional"))
      (node (ref "CON2") (pin "P24") (pinfunction "P24_P24") (pintype "bidirectional"))
    )
    (net (code "60") (name "Net-(15.3-PadP$1)") (class "Default")
      (node (ref "15.3") (pin "P$1") (pinfunction "P$1_P$1") (pintype "bidirectional"))
      (node (ref "CON2") (pin "P22") (pinfunction "P22_P22") (pintype "bidirectional"))
    )
    (net (code "61") (name "Net-(15.4-PadP$1)") (class "Default")
      (node (ref "15.4") (pin "P$1") (pinfunction "P$1_P$1") (pintype "bidirectional"))
      (node (ref "CON2") (pin "P20") (pinfunction "P20_P20") (pintype "bidirectional"))
    )
    (net (code "62") (name "Net-(16.1-PadP$1)") (class "Default")
      (node (ref "16.1") (pin "P$1") (pinfunction "P$1_P$1") (pintype "bidirectional"))
      (node (ref "CON2") (pin "P34") (pinfunction "P34_P34") (pintype "bidirectional"))
    )
    (net (code "63") (name "Net-(16.2-PadP$1)") (class "Default")
      (node (ref "16.2") (pin "P$1") (pinfunction "P$1_P$1") (pintype "bidirectional"))
      (node (ref "CON2") (pin "P32") (pinfunction "P32_P32") (pintype "bidirectional"))
    )
    (net (code "64") (name "Net-(16.3-PadP$1)") (class "Default")
      (node (ref "16.3") (pin "P$1") (pinfunction "P$1_P$1") (pintype "bidirectional"))
      (node (ref "CON2") (pin "P30") (pinfunction "P30_P30") (pintype "bidirectional"))
    )
    (net (code "65") (name "Net-(16.4-PadP$1)") (class "Default")
      (node (ref "16.4") (pin "P$1") (pinfunction "P$1_P$1") (pintype "bidirectional"))
      (node (ref "CON2") (pin "P28") (pinfunction "P28_P28") (pintype "bidirectional"))
    )
    (net (code "66") (name "Net-(17.1-PadP$1)") (class "Default")
      (node (ref "17.1") (pin "P$1") (pinfunction "P$1_P$1") (pintype "bidirectional"))
      (node (ref "CON3") (pin "P3") (pinfunction "P3_P3") (pintype "bidirectional"))
    )
    (net (code "67") (name "Net-(17.2-PadP$1)") (class "Default")
      (node (ref "17.2") (pin "P$1") (pinfunction "P$1_P$1") (pintype "bidirectional"))
      (node (ref "CON3") (pin "P5") (pinfunction "P5_P5") (pintype "bidirectional"))
    )
    (net (code "68") (name "Net-(17.3-PadP$1)") (class "Default")
      (node (ref "17.3") (pin "P$1") (pinfunction "P$1_P$1") (pintype "bidirectional"))
      (node (ref "CON3") (pin "P7") (pinfunction "P7_P7") (pintype "bidirectional"))
    )
    (net (code "69") (name "Net-(17.4-PadP$1)") (class "Default")
      (node (ref "17.4") (pin "P$1") (pinfunction "P$1_P$1") (pintype "bidirectional"))
      (node (ref "CON3") (pin "P9") (pinfunction "P9_P9") (pintype "bidirectional"))
    )
    (net (code "70") (name "Net-(18.1-PadP$1)") (class "Default")
      (node (ref "18.1") (pin "P$1") (pinfunction "P$1_P$1") (pintype "bidirectional"))
      (node (ref "CON3") (pin "P11") (pinfunction "P11_P11") (pintype "bidirectional"))
    )
    (net (code "71") (name "Net-(18.2-PadP$1)") (class "Default")
      (node (ref "18.2") (pin "P$1") (pinfunction "P$1_P$1") (pintype "bidirectional"))
      (node (ref "CON3") (pin "P13") (pinfunction "P13_P13") (pintype "bidirectional"))
    )
    (net (code "72") (name "Net-(18.3-PadP$1)") (class "Default")
      (node (ref "18.3") (pin "P$1") (pinfunction "P$1_P$1") (pintype "bidirectional"))
      (node (ref "CON3") (pin "P15") (pinfunction "P15_P15") (pintype "bidirectional"))
    )
    (net (code "73") (name "Net-(18.4-PadP$1)") (class "Default")
      (node (ref "18.4") (pin "P$1") (pinfunction "P$1_P$1") (pintype "bidirectional"))
      (node (ref "CON3") (pin "P17") (pinfunction "P17_P17") (pintype "bidirectional"))
    )
    (net (code "74") (name "Net-(19.1-PadP$1)") (class "Default")
      (node (ref "19.1") (pin "P$1") (pinfunction "P$1_P$1") (pintype "bidirectional"))
      (node (ref "CON3") (pin "P19") (pinfunction "P19_P19") (pintype "bidirectional"))
    )
    (net (code "75") (name "Net-(19.2-PadP$1)") (class "Default")
      (node (ref "19.2") (pin "P$1") (pinfunction "P$1_P$1") (pintype "bidirectional"))
      (node (ref "CON3") (pin "P21") (pinfunction "P21_P21") (pintype "bidirectional"))
    )
    (net (code "76") (name "Net-(19.3-PadP$1)") (class "Default")
      (node (ref "19.3") (pin "P$1") (pinfunction "P$1_P$1") (pintype "bidirectional"))
      (node (ref "CON3") (pin "P23") (pinfunction "P23_P23") (pintype "bidirectional"))
    )
    (net (code "77") (name "Net-(19.4-PadP$1)") (class "Default")
      (node (ref "19.4") (pin "P$1") (pinfunction "P$1_P$1") (pintype "bidirectional"))
      (node (ref "CON3") (pin "P25") (pinfunction "P25_P25") (pintype "bidirectional"))
    )
    (net (code "78") (name "Net-(20.1-PadP$1)") (class "Default")
      (node (ref "20.1") (pin "P$1") (pinfunction "P$1_P$1") (pintype "bidirectional"))
      (node (ref "CON3") (pin "P27") (pinfunction "P27_P27") (pintype "bidirectional"))
    )
    (net (code "79") (name "Net-(20.2-PadP$1)") (class "Default")
      (node (ref "20.2") (pin "P$1") (pinfunction "P$1_P$1") (pintype "bidirectional"))
      (node (ref "CON3") (pin "P29") (pinfunction "P29_P29") (pintype "bidirectional"))
    )
    (net (code "80") (name "Net-(20.3-PadP$1)") (class "Default")
      (node (ref "20.3") (pin "P$1") (pinfunction "P$1_P$1") (pintype "bidirectional"))
      (node (ref "CON3") (pin "P31") (pinfunction "P31_P31") (pintype "bidirectional"))
    )
    (net (code "81") (name "Net-(20.4-PadP$1)") (class "Default")
      (node (ref "20.4") (pin "P$1") (pinfunction "P$1_P$1") (pintype "bidirectional"))
      (node (ref "CON3") (pin "P33") (pinfunction "P33_P33") (pintype "bidirectional"))
    )
    (net (code "82") (name "Net-(21.1-PadP$1)") (class "Default")
      (node (ref "21.1") (pin "P$1") (pinfunction "P$1_P$1") (pintype "bidirectional"))
      (node (ref "CON3") (pin "P34") (pinfunction "P34_P34") (pintype "bidirectional"))
    )
    (net (code "83") (name "Net-(21.2-PadP$1)") (class "Default")
      (node (ref "21.2") (pin "P$1") (pinfunction "P$1_P$1") (pintype "bidirectional"))
      (node (ref "CON3") (pin "P32") (pinfunction "P32_P32") (pintype "bidirectional"))
    )
    (net (code "84") (name "Net-(21.3-PadP$1)") (class "Default")
      (node (ref "21.3") (pin "P$1") (pinfunction "P$1_P$1") (pintype "bidirectional"))
      (node (ref "CON3") (pin "P30") (pinfunction "P30_P30") (pintype "bidirectional"))
    )
    (net (code "85") (name "Net-(21.4-PadP$1)") (class "Default")
      (node (ref "21.4") (pin "P$1") (pinfunction "P$1_P$1") (pintype "bidirectional"))
      (node (ref "CON3") (pin "P28") (pinfunction "P28_P28") (pintype "bidirectional"))
    )
    (net (code "86") (name "Net-(22.1-PadP$1)") (class "Default")
      (node (ref "22.1") (pin "P$1") (pinfunction "P$1_P$1") (pintype "bidirectional"))
      (node (ref "CON3") (pin "P26") (pinfunction "P26_P26") (pintype "bidirectional"))
    )
    (net (code "87") (name "Net-(22.2-PadP$1)") (class "Default")
      (node (ref "22.2") (pin "P$1") (pinfunction "P$1_P$1") (pintype "bidirectional"))
      (node (ref "CON3") (pin "P24") (pinfunction "P24_P24") (pintype "bidirectional"))
    )
    (net (code "88") (name "Net-(22.3-PadP$1)") (class "Default")
      (node (ref "22.3") (pin "P$1") (pinfunction "P$1_P$1") (pintype "bidirectional"))
      (node (ref "CON3") (pin "P22") (pinfunction "P22_P22") (pintype "bidirectional"))
    )
    (net (code "89") (name "Net-(22.4-PadP$1)") (class "Default")
      (node (ref "22.4") (pin "P$1") (pinfunction "P$1_P$1") (pintype "bidirectional"))
      (node (ref "CON3") (pin "P20") (pinfunction "P20_P20") (pintype "bidirectional"))
    )
    (net (code "90") (name "Net-(23.1-PadP$1)") (class "Default")
      (node (ref "23.1") (pin "P$1") (pinfunction "P$1_P$1") (pintype "bidirectional"))
      (node (ref "CON3") (pin "P18") (pinfunction "P18_P18") (pintype "bidirectional"))
    )
    (net (code "91") (name "Net-(23.2-PadP$1)") (class "Default")
      (node (ref "23.2") (pin "P$1") (pinfunction "P$1_P$1") (pintype "bidirectional"))
      (node (ref "CON3") (pin "P16") (pinfunction "P16_P16") (pintype "bidirectional"))
    )
    (net (code "92") (name "Net-(23.3-PadP$1)") (class "Default")
      (node (ref "23.3") (pin "P$1") (pinfunction "P$1_P$1") (pintype "bidirectional"))
      (node (ref "CON3") (pin "P14") (pinfunction "P14_P14") (pintype "bidirectional"))
    )
    (net (code "93") (name "Net-(23.4-PadP$1)") (class "Default")
      (node (ref "23.4") (pin "P$1") (pinfunction "P$1_P$1") (pintype "bidirectional"))
      (node (ref "CON3") (pin "P12") (pinfunction "P12_P12") (pintype "bidirectional"))
    )
    (net (code "94") (name "Net-(24.1-PadP$1)") (class "Default")
      (node (ref "24.1") (pin "P$1") (pinfunction "P$1_P$1") (pintype "bidirectional"))
      (node (ref "CON3") (pin "P10") (pinfunction "P10_P10") (pintype "bidirectional"))
    )
    (net (code "95") (name "Net-(24.2-PadP$1)") (class "Default")
      (node (ref "24.2") (pin "P$1") (pinfunction "P$1_P$1") (pintype "bidirectional"))
      (node (ref "CON3") (pin "P8") (pinfunction "P8_P8") (pintype "bidirectional"))
    )
    (net (code "96") (name "Net-(24.3-PadP$1)") (class "Default")
      (node (ref "24.3") (pin "P$1") (pinfunction "P$1_P$1") (pintype "bidirectional"))
      (node (ref "CON3") (pin "P6") (pinfunction "P6_P6") (pintype "bidirectional"))
    )
    (net (code "97") (name "Net-(24.4-PadP$1)") (class "Default")
      (node (ref "24.4") (pin "P$1") (pinfunction "P$1_P$1") (pintype "bidirectional"))
      (node (ref "CON3") (pin "P4") (pinfunction "P4_P4") (pintype "bidirectional"))
    )
    (net (code "98") (name "Net-(CON1-PadP2)") (class "Default")
      (node (ref "CON1") (pin "P2") (pinfunction "P2_P2") (pintype "bidirectional"))
      (node (ref "R1") (pin "P$1") (pinfunction "P$1_P$1") (pintype "bidirectional"))
    )
    (net (code "99") (name "Net-(CON1-PadP35)") (class "Default")
      (node (ref "CON1") (pin "P35") (pinfunction "P35_P35") (pintype "bidirectional"))
      (node (ref "R2") (pin "P$1") (pinfunction "P$1_P$1") (pintype "bidirectional"))
    )
    (net (code "100") (name "Net-(CON2-PadP2)") (class "Default")
      (node (ref "CON2") (pin "P2") (pinfunction "P2_P2") (pintype "bidirectional"))
      (node (ref "R3") (pin "P$1") (pinfunction "P$1_P$1") (pintype "bidirectional"))
    )
    (net (code "101") (name "Net-(CON2-PadP35)") (class "Default")
      (node (ref "CON2") (pin "P35") (pinfunction "P35_P35") (pintype "bidirectional"))
      (node (ref "R4") (pin "P$1") (pinfunction "P$1_P$1") (pintype "bidirectional"))
    )
    (net (code "102") (name "Net-(CON3-PadP2)") (class "Default")
      (node (ref "CON3") (pin "P2") (pinfunction "P2_P2") (pintype "bidirectional"))
      (node (ref "R6") (pin "P$1") (pinfunction "P$1_P$1") (pintype "bidirectional"))
    )
    (net (code "103") (name "Net-(CON3-PadP35)") (class "Default")
      (node (ref "CON3") (pin "P35") (pinfunction "P35_P35") (pintype "bidirectional"))
      (node (ref "R5") (pin "P$1") (pinfunction "P$1_P$1") (pintype "bidirectional"))
    )
  )
)
